# avr5.net
KiCad netlist of a schematic drawn in EAGLE
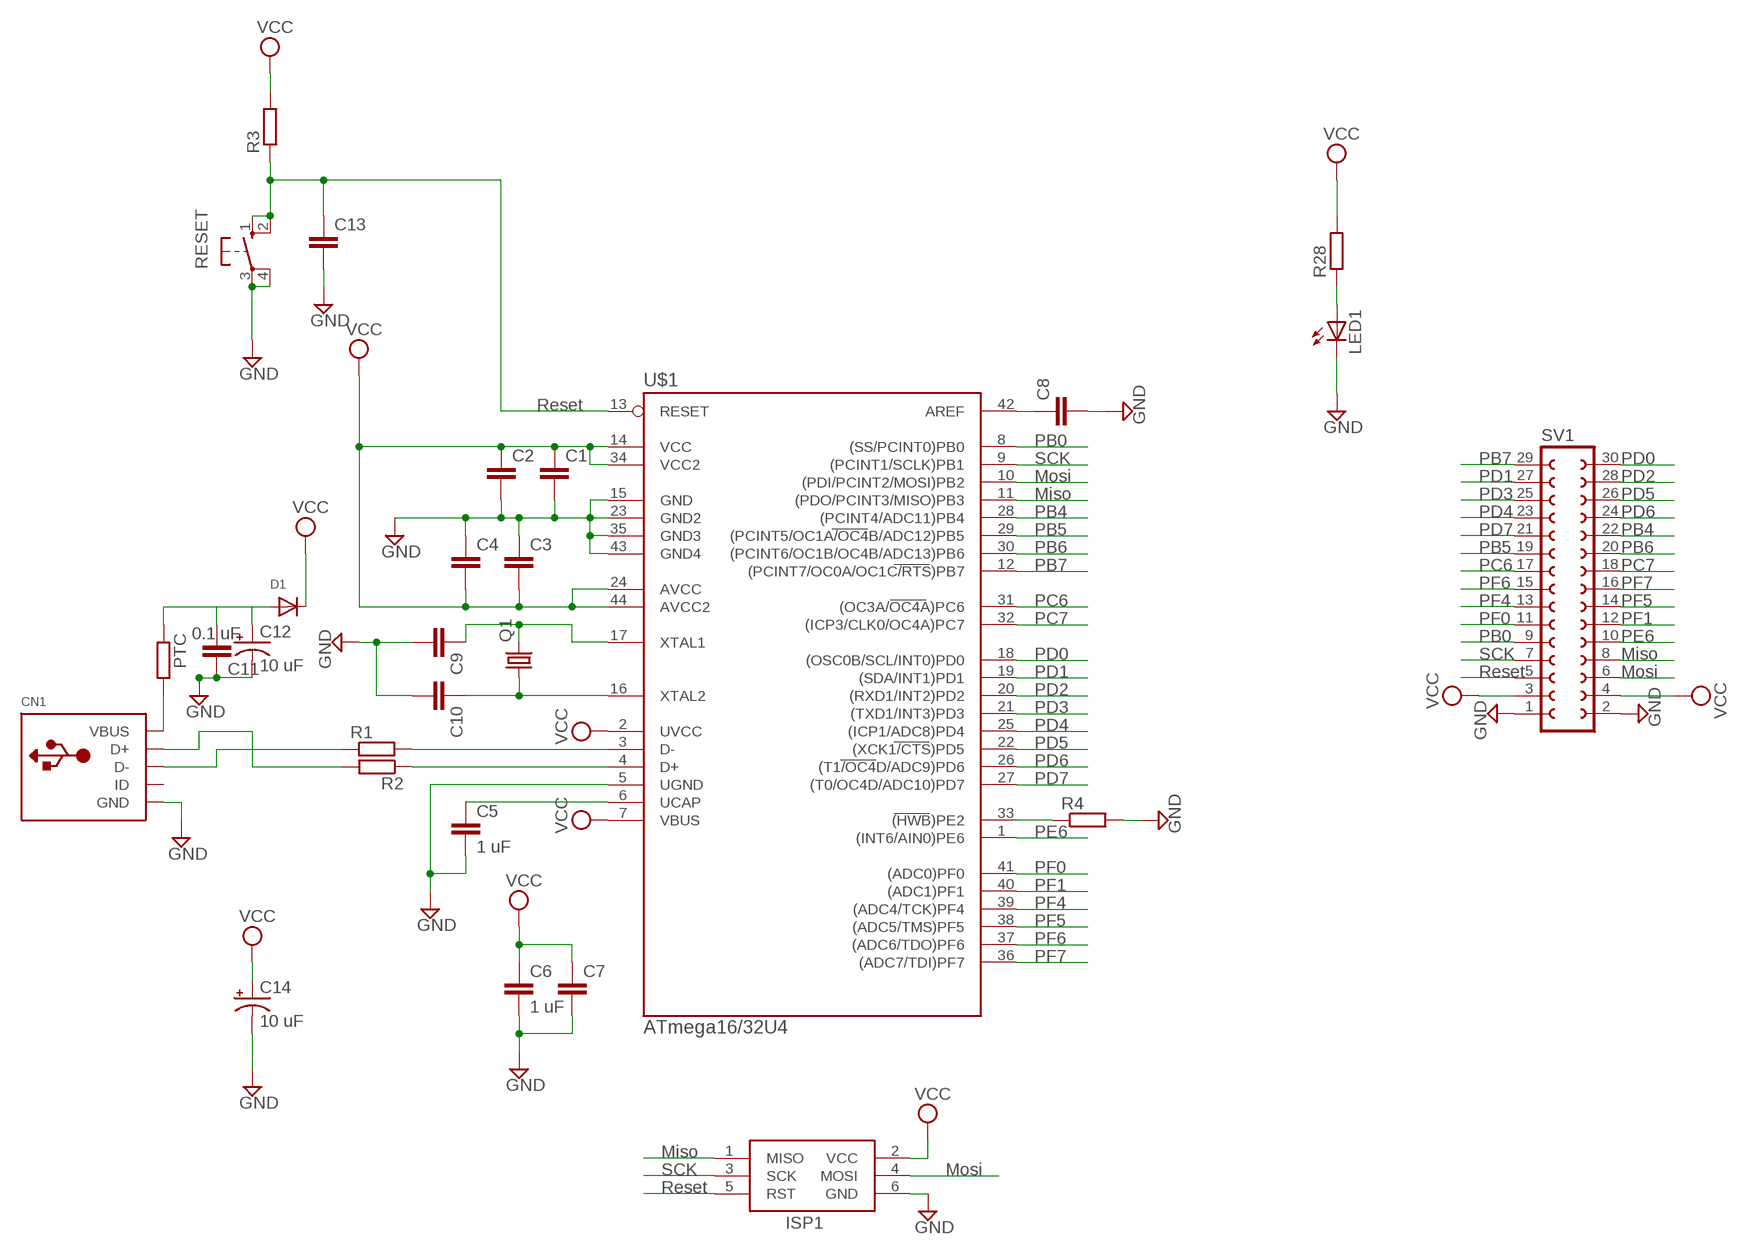
[diagram p0: schematic, sheet 1]

(export (version "E")
  (design (tool "Eeschema 10.0.6"))
  (components
    (comp (ref "C1")
      (value "C-EUC1206")
      (footprint "eagle-import:C1206")
      (libsource (lib "eagle-import") (part "C-EUC1206"))
    )
    (comp (ref "C2")
      (value "C-EUC1206")
      (footprint "eagle-import:C1206")
      (libsource (lib "eagle-import") (part "C-EUC1206"))
    )
    (comp (ref "C3")
      (value "C-EUC1206")
      (footprint "eagle-import:C1206")
      (libsource (lib "eagle-import") (part "C-EUC1206"))
    )
    (comp (ref "C4")
      (value "C-EUC1206")
      (footprint "eagle-import:C1206")
      (libsource (lib "eagle-import") (part "C-EUC1206"))
    )
    (comp (ref "C5")
      (value "1 uF")
      (footprint "eagle-import:C1206")
      (libsource (lib "eagle-import") (part "C-EUC1206"))
    )
    (comp (ref "C6")
      (value "1 uF")
      (footprint "eagle-import:C1206")
      (libsource (lib "eagle-import") (part "C-EUC1206"))
    )
    (comp (ref "C7")
      (value "C-EUC1206")
      (footprint "eagle-import:C1206")
      (libsource (lib "eagle-import") (part "C-EUC1206"))
    )
    (comp (ref "C8")
      (value "C-EUC1206")
      (footprint "eagle-import:C1206")
      (libsource (lib "eagle-import") (part "C-EUC1206"))
    )
    (comp (ref "C9")
      (value "C-EUC1206")
      (footprint "eagle-import:C1206")
      (libsource (lib "eagle-import") (part "C-EUC1206"))
    )
    (comp (ref "C10")
      (value "C-EUC1206")
      (footprint "eagle-import:C1206")
      (libsource (lib "eagle-import") (part "C-EUC1206"))
    )
    (comp (ref "C11")
      (value "0.1 uF")
      (footprint "eagle-import:C1206")
      (libsource (lib "eagle-import") (part "C-EUC1206"))
    )
    (comp (ref "C12")
      (value "10 uF")
      (footprint "eagle-import:EIA3216")
      (libsource (lib "eagle-import") (part "CAP_POL1206"))
    )
    (comp (ref "C13")
      (value "C-EUC1206")
      (footprint "eagle-import:C1206")
      (libsource (lib "eagle-import") (part "C-EUC1206"))
    )
    (comp (ref "C14")
      (value "10 uF")
      (footprint "eagle-import:EIA3216")
      (libsource (lib "eagle-import") (part "CAP_POL1206"))
    )
    (comp (ref "CN1")
      (value "USBMINIB")
      (footprint "eagle-import:USB-MINIB")
      (libsource (lib "eagle-import") (part "USBMINIB"))
    )
    (comp (ref "D1")
      (value "DIODESOD-123")
      (footprint "eagle-import:SOD-123")
      (libsource (lib "eagle-import") (part "DIODESOD-123"))
    )
    (comp (ref "ISP1")
      (value "AVRISP-6")
      (footprint "eagle-import:AVRISP")
      (libsource (lib "eagle-import") (part "AVRISP-6"))
    )
    (comp (ref "LED1")
      (value "LEDCHIPLED_1206")
      (footprint "eagle-import:CHIPLED_1206")
      (libsource (lib "eagle-import") (part "LEDCHIPLED_1206"))
    )
    (comp (ref "PTC")
      (value "R-EU_R1206")
      (footprint "eagle-import:R1206")
      (libsource (lib "eagle-import") (part "R-EU_R1206"))
    )
    (comp (ref "Q1")
      (value "CRYSTALHC49UP")
      (footprint "eagle-import:HC49UP")
      (fields (field (name "OC_FARNELL") "unknown") (field (name "OC_NEWARK") "unknown"))
      (libsource (lib "eagle-import") (part "CRYSTALHC49UP"))
    )
    (comp (ref "R1")
      (value "R-EU_R1206")
      (footprint "eagle-import:R1206")
      (libsource (lib "eagle-import") (part "R-EU_R1206"))
    )
    (comp (ref "R2")
      (value "R-EU_R1206")
      (footprint "eagle-import:R1206")
      (libsource (lib "eagle-import") (part "R-EU_R1206"))
    )
    (comp (ref "R3")
      (value "R-EU_R1206")
      (footprint "eagle-import:R1206")
      (libsource (lib "eagle-import") (part "R-EU_R1206"))
    )
    (comp (ref "R4")
      (value "R-EU_R1206")
      (footprint "eagle-import:R1206")
      (libsource (lib "eagle-import") (part "R-EU_R1206"))
    )
    (comp (ref "R28")
      (value "R-EU_R1206")
      (footprint "eagle-import:R1206")
      (libsource (lib "eagle-import") (part "R-EU_R1206"))
    )
    (comp (ref "RESET")
      (value "10-XX")
      (footprint "eagle-import:B3F-10XX")
      (fields (field (name "MPN") "B3F-1000"))
      (libsource (lib "eagle-import") (part "10-XX"))
    )
    (comp (ref "SV1")
      (value "FE15-2")
      (footprint "eagle-import:FE15-2")
      (libsource (lib "eagle-import") (part "FE15-2"))
    )
    (comp (ref "U$1")
      (value "ATmega16/32U4")
      (footprint "eagle-import:TQFP44")
      (libsource (lib "eagle-import") (part "ATMEGA32U4-AU"))
    )
  )
  (nets
    (net (code "1") (name "/MISO") (class "Default")
      (node (ref "ISP1") (pin "1") (pinfunction "MISO_1") (pintype "input"))
      (node (ref "SV1") (pin "8") (pinfunction "8_8") (pintype "passive"))
      (node (ref "U$1") (pin "11") (pinfunction "(PDO/PCINT3/MISO)PB3_11") (pintype "bidirectional"))
    )
    (net (code "2") (name "/MOSI") (class "Default")
      (node (ref "ISP1") (pin "4") (pinfunction "MOSI_4") (pintype "output"))
      (node (ref "SV1") (pin "6") (pinfunction "6_6") (pintype "passive"))
      (node (ref "U$1") (pin "10") (pinfunction "(PDI/PCINT2/MOSI)PB2_10") (pintype "bidirectional"))
    )
    (net (code "3") (name "/PB0") (class "Default")
      (node (ref "SV1") (pin "9") (pinfunction "9_9") (pintype "passive"))
      (node (ref "U$1") (pin "8") (pinfunction "(SS/PCINT0)PB0_8") (pintype "bidirectional"))
    )
    (net (code "4") (name "/PB4") (class "Default")
      (node (ref "SV1") (pin "22") (pinfunction "22_22") (pintype "passive"))
      (node (ref "U$1") (pin "28") (pinfunction "(PCINT4/ADC11)PB4_28") (pintype "bidirectional"))
    )
    (net (code "5") (name "/PB5") (class "Default")
      (node (ref "SV1") (pin "19") (pinfunction "19_19") (pintype "passive"))
      (node (ref "U$1") (pin "29") (pinfunction "(PCINT5/OC1A/OC4B/ADC12)PB5_29") (pintype "bidirectional"))
    )
    (net (code "6") (name "/PB6") (class "Default")
      (node (ref "SV1") (pin "20") (pinfunction "20_20") (pintype "passive"))
      (node (ref "U$1") (pin "30") (pinfunction "(PCINT6/OC1B/OC4B/ADC13)PB6_30") (pintype "bidirectional"))
    )
    (net (code "7") (name "/PB7") (class "Default")
      (node (ref "SV1") (pin "29") (pinfunction "29_29") (pintype "passive"))
      (node (ref "U$1") (pin "12") (pinfunction "(PCINT7/OC0A/OC1C/RTS)PB7_12") (pintype "bidirectional"))
    )
    (net (code "8") (name "/PC6") (class "Default")
      (node (ref "SV1") (pin "17") (pinfunction "17_17") (pintype "passive"))
      (node (ref "U$1") (pin "31") (pinfunction "(OC3A/OC4A)PC6_31") (pintype "bidirectional"))
    )
    (net (code "9") (name "/PC7") (class "Default")
      (node (ref "SV1") (pin "18") (pinfunction "18_18") (pintype "passive"))
      (node (ref "U$1") (pin "32") (pinfunction "(ICP3/CLK0/OC4A)PC7_32") (pintype "bidirectional"))
    )
    (net (code "10") (name "/PD0") (class "Default")
      (node (ref "SV1") (pin "30") (pinfunction "30_30") (pintype "passive"))
      (node (ref "U$1") (pin "18") (pinfunction "(OSC0B/SCL/INT0)PD0_18") (pintype "bidirectional"))
    )
    (net (code "11") (name "/PD1") (class "Default")
      (node (ref "SV1") (pin "27") (pinfunction "27_27") (pintype "passive"))
      (node (ref "U$1") (pin "19") (pinfunction "(SDA/INT1)PD1_19") (pintype "bidirectional"))
    )
    (net (code "12") (name "/PD2") (class "Default")
      (node (ref "SV1") (pin "28") (pinfunction "28_28") (pintype "passive"))
      (node (ref "U$1") (pin "20") (pinfunction "(RXD1/INT2)PD2_20") (pintype "bidirectional"))
    )
    (net (code "13") (name "/PD3") (class "Default")
      (node (ref "SV1") (pin "25") (pinfunction "25_25") (pintype "passive"))
      (node (ref "U$1") (pin "21") (pinfunction "(TXD1/INT3)PD3_21") (pintype "bidirectional"))
    )
    (net (code "14") (name "/PD4") (class "Default")
      (node (ref "SV1") (pin "23") (pinfunction "23_23") (pintype "passive"))
      (node (ref "U$1") (pin "25") (pinfunction "(ICP1/ADC8)PD4_25") (pintype "bidirectional"))
    )
    (net (code "15") (name "/PD5") (class "Default")
      (node (ref "SV1") (pin "26") (pinfunction "26_26") (pintype "passive"))
      (node (ref "U$1") (pin "22") (pinfunction "(XCK1/CTS)PD5_22") (pintype "bidirectional"))
    )
    (net (code "16") (name "/PD6") (class "Default")
      (node (ref "SV1") (pin "24") (pinfunction "24_24") (pintype "passive"))
      (node (ref "U$1") (pin "26") (pinfunction "(T1/OC4D/ADC9)PD6_26") (pintype "bidirectional"))
    )
    (net (code "17") (name "/PD7") (class "Default")
      (node (ref "SV1") (pin "21") (pinfunction "21_21") (pintype "passive"))
      (node (ref "U$1") (pin "27") (pinfunction "(T0/OC4D/ADC10)PD7_27") (pintype "bidirectional"))
    )
    (net (code "18") (name "/PE6") (class "Default")
      (node (ref "SV1") (pin "10") (pinfunction "10_10") (pintype "passive"))
      (node (ref "U$1") (pin "1") (pinfunction "(INT6/AIN0)PE6_1") (pintype "bidirectional"))
    )
    (net (code "19") (name "/PF0") (class "Default")
      (node (ref "SV1") (pin "11") (pinfunction "11_11") (pintype "passive"))
      (node (ref "U$1") (pin "41") (pinfunction "(ADC0)PF0_41") (pintype "bidirectional"))
    )
    (net (code "20") (name "/PF1") (class "Default")
      (node (ref "SV1") (pin "12") (pinfunction "12_12") (pintype "passive"))
      (node (ref "U$1") (pin "40") (pinfunction "(ADC1)PF1_40") (pintype "bidirectional"))
    )
    (net (code "21") (name "/PF4") (class "Default")
      (node (ref "SV1") (pin "13") (pinfunction "13_13") (pintype "passive"))
      (node (ref "U$1") (pin "39") (pinfunction "(ADC4/TCK)PF4_39") (pintype "bidirectional"))
    )
    (net (code "22") (name "/PF5") (class "Default")
      (node (ref "SV1") (pin "14") (pinfunction "14_14") (pintype "passive"))
      (node (ref "U$1") (pin "38") (pinfunction "(ADC5/TMS)PF5_38") (pintype "bidirectional"))
    )
    (net (code "23") (name "/PF6") (class "Default")
      (node (ref "SV1") (pin "15") (pinfunction "15_15") (pintype "passive"))
      (node (ref "U$1") (pin "37") (pinfunction "(ADC6/TDO)PF6_37") (pintype "bidirectional"))
    )
    (net (code "24") (name "/PF7") (class "Default")
      (node (ref "SV1") (pin "16") (pinfunction "16_16") (pintype "passive"))
      (node (ref "U$1") (pin "36") (pinfunction "(ADC7/TDI)PF7_36") (pintype "bidirectional"))
    )
    (net (code "25") (name "/RESET") (class "Default")
      (node (ref "C13") (pin "1") (pinfunction "1_1") (pintype "passive"))
      (node (ref "ISP1") (pin "5") (pinfunction "RST_5") (pintype "output"))
      (node (ref "R3") (pin "1") (pinfunction "1_1") (pintype "passive"))
      (node (ref "RESET") (pin "1") (pinfunction "S_1") (pintype "passive"))
      (node (ref "RESET") (pin "2") (pinfunction "S1_2") (pintype "passive"))
      (node (ref "SV1") (pin "5") (pinfunction "5_5") (pintype "passive"))
      (node (ref "U$1") (pin "13") (pinfunction "RESET_13") (pintype "bidirectional"))
    )
    (net (code "26") (name "/SCK") (class "Default")
      (node (ref "ISP1") (pin "3") (pinfunction "SCK_3") (pintype "output"))
      (node (ref "SV1") (pin "7") (pinfunction "7_7") (pintype "passive"))
      (node (ref "U$1") (pin "9") (pinfunction "(PCINT1/SCLK)PB1_9") (pintype "bidirectional"))
    )
    (net (code "27") (name "GND") (class "Default")
      (node (ref "C1") (pin "2") (pinfunction "2_2") (pintype "passive"))
      (node (ref "C10") (pin "2") (pinfunction "2_2") (pintype "passive"))
      (node (ref "C11") (pin "2") (pinfunction "2_2") (pintype "passive"))
      (node (ref "C12") (pin "C") (pinfunction "-_C") (pintype "passive"))
      (node (ref "C13") (pin "2") (pinfunction "2_2") (pintype "passive"))
      (node (ref "C14") (pin "C") (pinfunction "-_C") (pintype "passive"))
      (node (ref "C2") (pin "2") (pinfunction "2_2") (pintype "passive"))
      (node (ref "C3") (pin "1") (pinfunction "1_1") (pintype "passive"))
      (node (ref "C4") (pin "1") (pinfunction "1_1") (pintype "passive"))
      (node (ref "C5") (pin "2") (pinfunction "2_2") (pintype "passive"))
      (node (ref "C6") (pin "2") (pinfunction "2_2") (pintype "passive"))
      (node (ref "C7") (pin "2") (pinfunction "2_2") (pintype "passive"))
      (node (ref "C8") (pin "2") (pinfunction "2_2") (pintype "passive"))
      (node (ref "C9") (pin "2") (pinfunction "2_2") (pintype "passive"))
      (node (ref "CN1") (pin "GND") (pinfunction "GND_GND") (pintype "power_in"))
      (node (ref "ISP1") (pin "6") (pinfunction "GND_6") (pintype "power_in"))
      (node (ref "LED1") (pin "C") (pinfunction "C_C") (pintype "passive"))
      (node (ref "R4") (pin "2") (pinfunction "2_2") (pintype "passive"))
      (node (ref "RESET") (pin "3") (pinfunction "P_3") (pintype "passive"))
      (node (ref "RESET") (pin "4") (pinfunction "P1_4") (pintype "passive"))
      (node (ref "SV1") (pin "1") (pinfunction "1_1") (pintype "passive"))
      (node (ref "SV1") (pin "2") (pinfunction "2_2") (pintype "passive"))
      (node (ref "U$1") (pin "15") (pinfunction "GND_15") (pintype "bidirectional"))
      (node (ref "U$1") (pin "23") (pinfunction "GND2_23") (pintype "bidirectional"))
      (node (ref "U$1") (pin "35") (pinfunction "GND3_35") (pintype "bidirectional"))
      (node (ref "U$1") (pin "43") (pinfunction "GND4_43") (pintype "bidirectional"))
      (node (ref "U$1") (pin "5") (pinfunction "UGND_5") (pintype "bidirectional"))
    )
    (net (code "28") (name "Net-(C12-+)") (class "Default")
      (node (ref "C11") (pin "1") (pinfunction "1_1") (pintype "passive"))
      (node (ref "C12") (pin "A") (pinfunction "+_A") (pintype "passive"))
      (node (ref "D1") (pin "A") (pinfunction "A_A") (pintype "passive"))
      (node (ref "PTC") (pin "1") (pinfunction "1_1") (pintype "passive"))
    )
    (net (code "29") (name "Net-(CN1-PadD+)") (class "Default")
      (node (ref "CN1") (pin "D+") (pinfunction "D+_D+") (pintype "bidirectional"))
      (node (ref "R2") (pin "2") (pinfunction "2_2") (pintype "passive"))
    )
    (net (code "30") (name "Net-(CN1-PadD-)") (class "Default")
      (node (ref "CN1") (pin "D-") (pinfunction "D-_D-") (pintype "bidirectional"))
      (node (ref "R1") (pin "1") (pinfunction "1_1") (pintype "passive"))
    )
    (net (code "31") (name "Net-(CN1-PadVBUS)") (class "Default")
      (node (ref "CN1") (pin "VBUS") (pinfunction "VBUS_VBUS") (pintype "power_in"))
      (node (ref "PTC") (pin "2") (pinfunction "2_2") (pintype "passive"))
    )
    (net (code "32") (name "Net-(LED1-PadA)") (class "Default")
      (node (ref "LED1") (pin "A") (pinfunction "A_A") (pintype "passive"))
      (node (ref "R28") (pin "1") (pinfunction "1_1") (pintype "passive"))
    )
    (net (code "33") (name "Net-(U$1-(HWB)PE2)") (class "Default")
      (node (ref "R4") (pin "1") (pinfunction "1_1") (pintype "passive"))
      (node (ref "U$1") (pin "33") (pinfunction "(HWB)PE2_33") (pintype "bidirectional"))
    )
    (net (code "34") (name "Net-(U$1-AREF)") (class "Default")
      (node (ref "C8") (pin "1") (pinfunction "1_1") (pintype "passive"))
      (node (ref "U$1") (pin "42") (pinfunction "AREF_42") (pintype "bidirectional"))
    )
    (net (code "35") (name "Net-(U$1-D+)") (class "Default")
      (node (ref "R2") (pin "1") (pinfunction "1_1") (pintype "passive"))
      (node (ref "U$1") (pin "4") (pinfunction "D+_4") (pintype "bidirectional"))
    )
    (net (code "36") (name "Net-(U$1-D-)") (class "Default")
      (node (ref "R1") (pin "2") (pinfunction "2_2") (pintype "passive"))
      (node (ref "U$1") (pin "3") (pinfunction "D-_3") (pintype "bidirectional"))
    )
    (net (code "37") (name "Net-(U$1-UCAP)") (class "Default")
      (node (ref "C5") (pin "1") (pinfunction "1_1") (pintype "passive"))
      (node (ref "U$1") (pin "6") (pinfunction "UCAP_6") (pintype "bidirectional"))
    )
    (net (code "38") (name "Net-(U$1-XTAL1)") (class "Default")
      (node (ref "C9") (pin "1") (pinfunction "1_1") (pintype "passive"))
      (node (ref "Q1") (pin "2") (pinfunction "2_2") (pintype "passive"))
      (node (ref "U$1") (pin "17") (pinfunction "XTAL1_17") (pintype "bidirectional"))
    )
    (net (code "39") (name "Net-(U$1-XTAL2)") (class "Default")
      (node (ref "C10") (pin "1") (pinfunction "1_1") (pintype "passive"))
      (node (ref "Q1") (pin "1") (pinfunction "1_1") (pintype "passive"))
      (node (ref "U$1") (pin "16") (pinfunction "XTAL2_16") (pintype "bidirectional"))
    )
    (net (code "40") (name "VCC") (class "Default")
      (node (ref "C1") (pin "1") (pinfunction "1_1") (pintype "passive"))
      (node (ref "C14") (pin "A") (pinfunction "+_A") (pintype "passive"))
      (node (ref "C2") (pin "1") (pinfunction "1_1") (pintype "passive"))
      (node (ref "C3") (pin "2") (pinfunction "2_2") (pintype "passive"))
      (node (ref "C4") (pin "2") (pinfunction "2_2") (pintype "passive"))
      (node (ref "C6") (pin "1") (pinfunction "1_1") (pintype "passive"))
      (node (ref "C7") (pin "1") (pinfunction "1_1") (pintype "passive"))
      (node (ref "D1") (pin "C") (pinfunction "C_C") (pintype "passive"))
      (node (ref "ISP1") (pin "2") (pinfunction "VCC_2") (pintype "power_in"))
      (node (ref "R28") (pin "2") (pinfunction "2_2") (pintype "passive"))
      (node (ref "R3") (pin "2") (pinfunction "2_2") (pintype "passive"))
      (node (ref "SV1") (pin "3") (pinfunction "3_3") (pintype "passive"))
      (node (ref "SV1") (pin "4") (pinfunction "4_4") (pintype "passive"))
      (node (ref "U$1") (pin "14") (pinfunction "VCC_14") (pintype "bidirectional"))
      (node (ref "U$1") (pin "2") (pinfunction "UVCC_2") (pintype "bidirectional"))
      (node (ref "U$1") (pin "24") (pinfunction "AVCC_24") (pintype "bidirectional"))
      (node (ref "U$1") (pin "34") (pinfunction "VCC2_34") (pintype "bidirectional"))
      (node (ref "U$1") (pin "44") (pinfunction "AVCC2_44") (pintype "bidirectional"))
      (node (ref "U$1") (pin "7") (pinfunction "VBUS_7") (pintype "bidirectional"))
    )
    (net (code "41") (name "unconnected-(CN1-PadID)") (class "Default")
      (node (ref "CN1") (pin "ID") (pinfunction "ID_ID") (pintype "bidirectional"))
    )
  )
)
